# ltc1420_adc.net
KiCad netlist of a schematic drawn in EAGLE
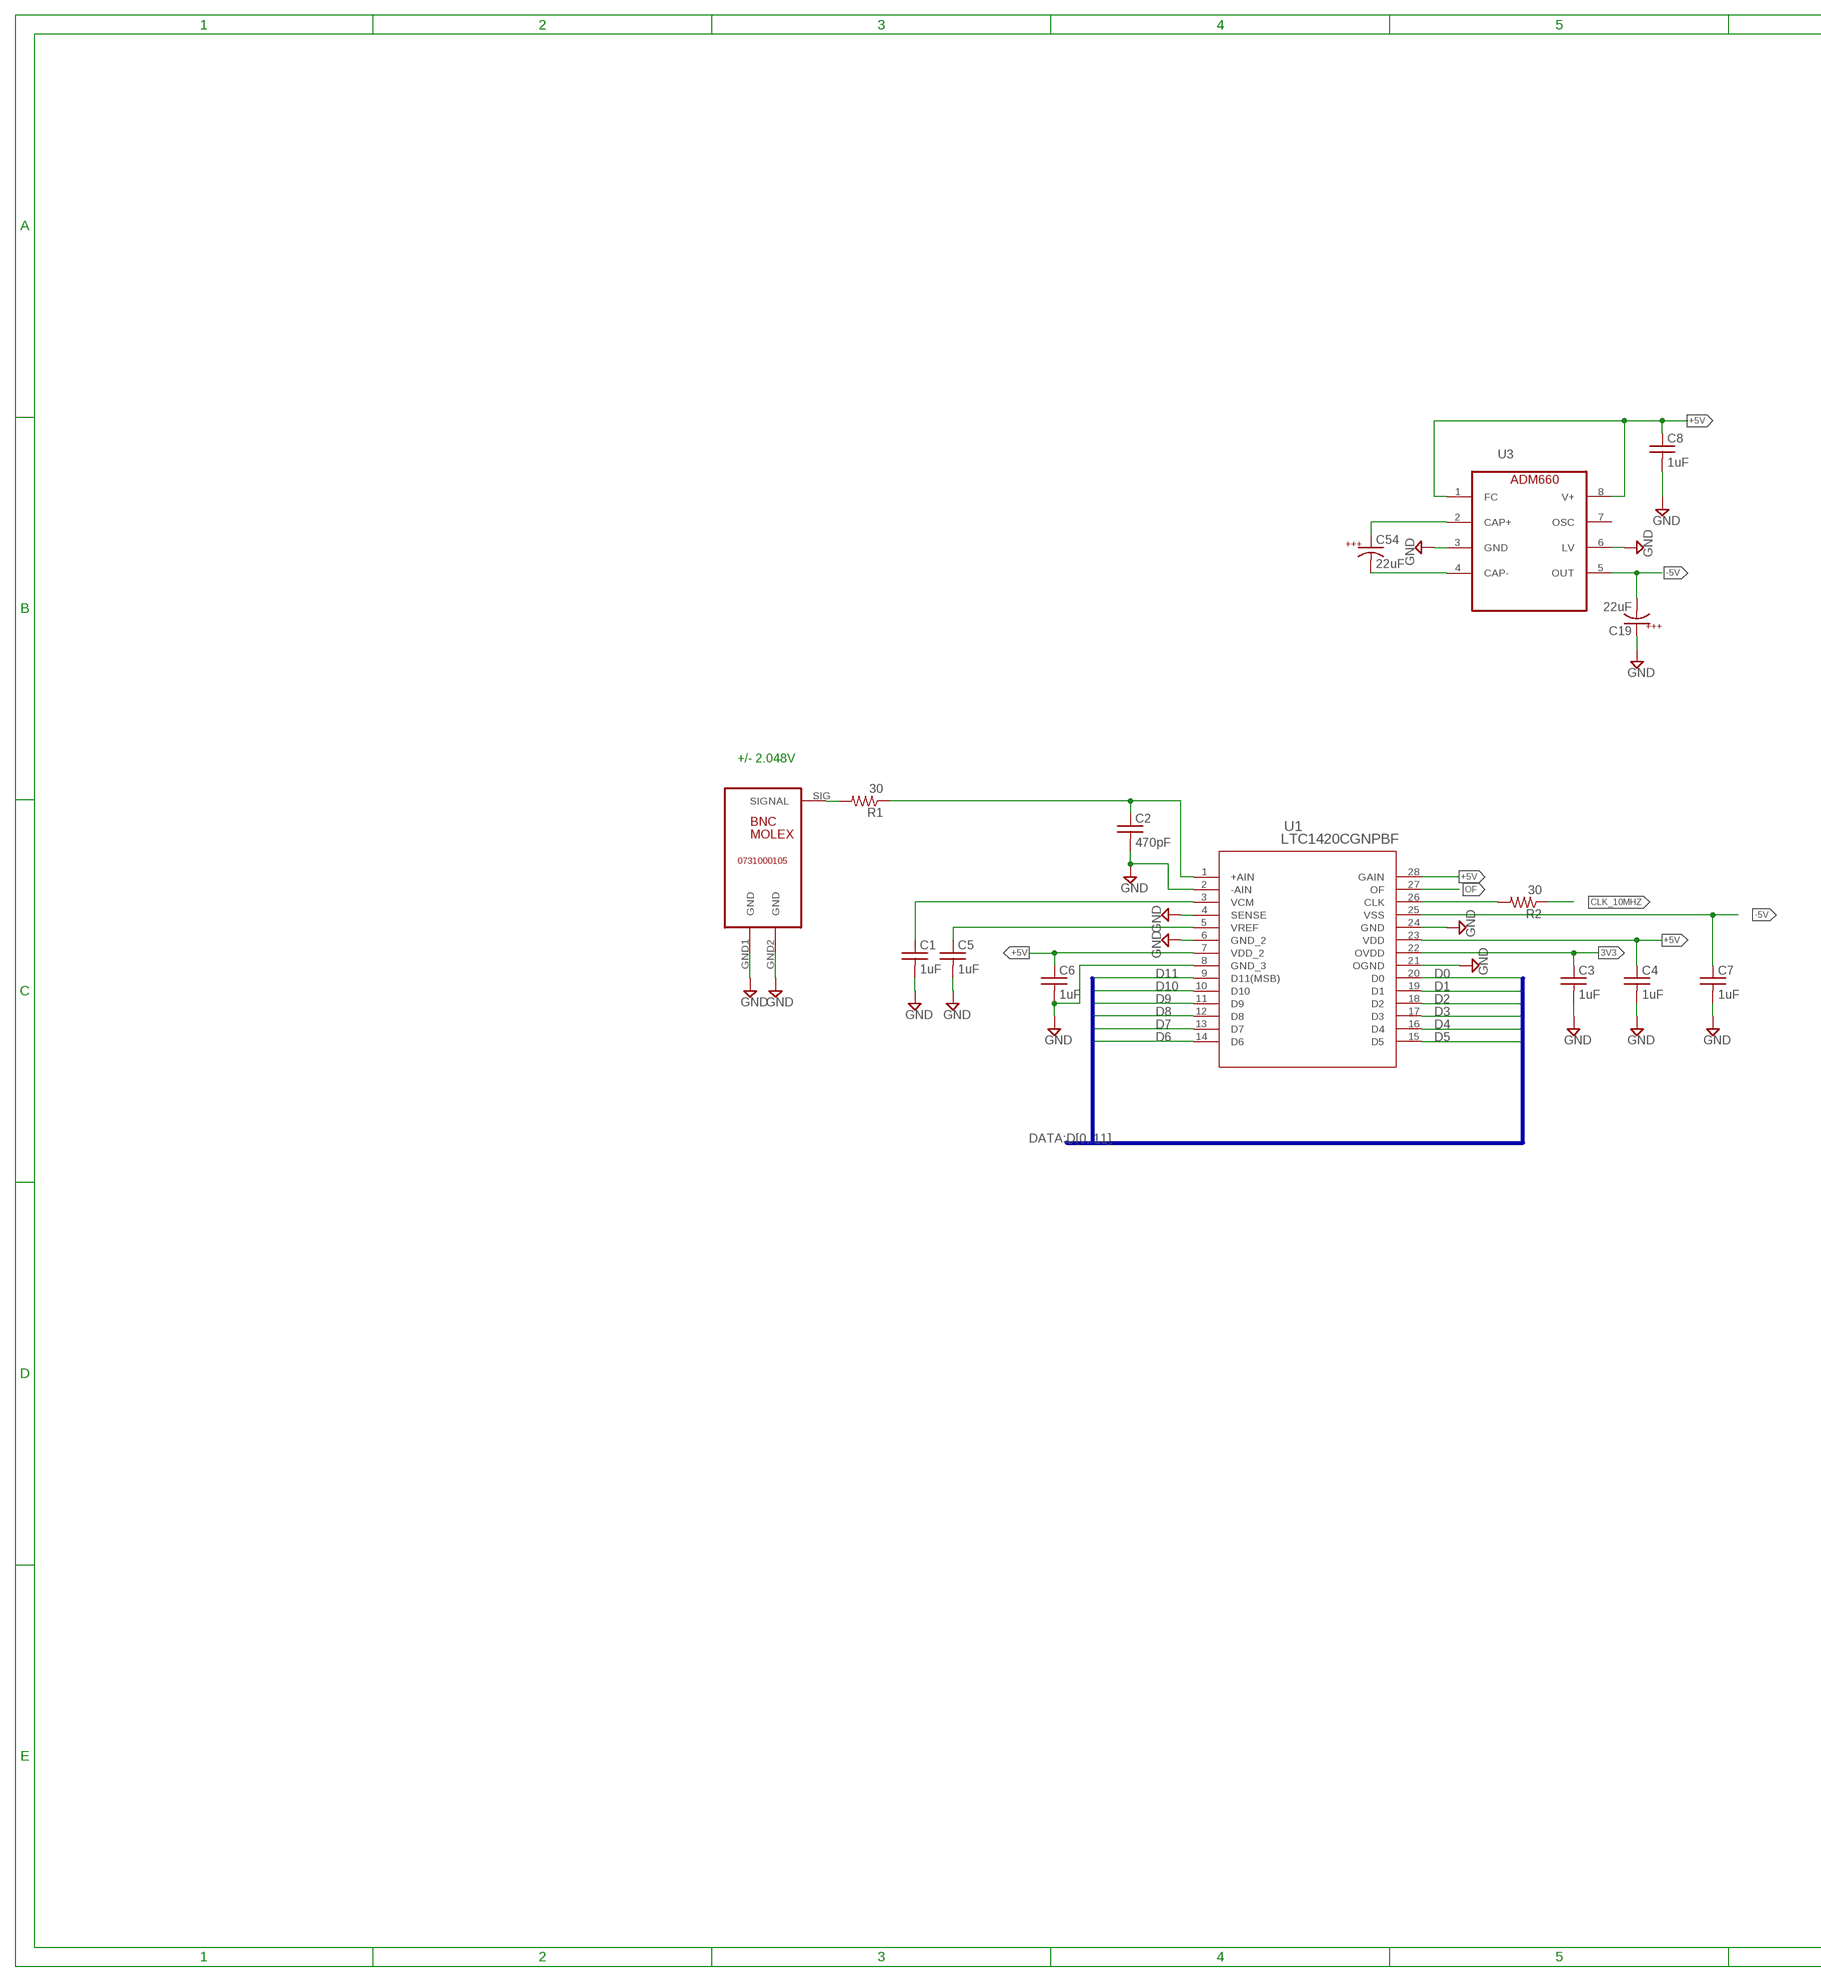
[diagram p0: schematic, sheet 1, part 1 of 2]
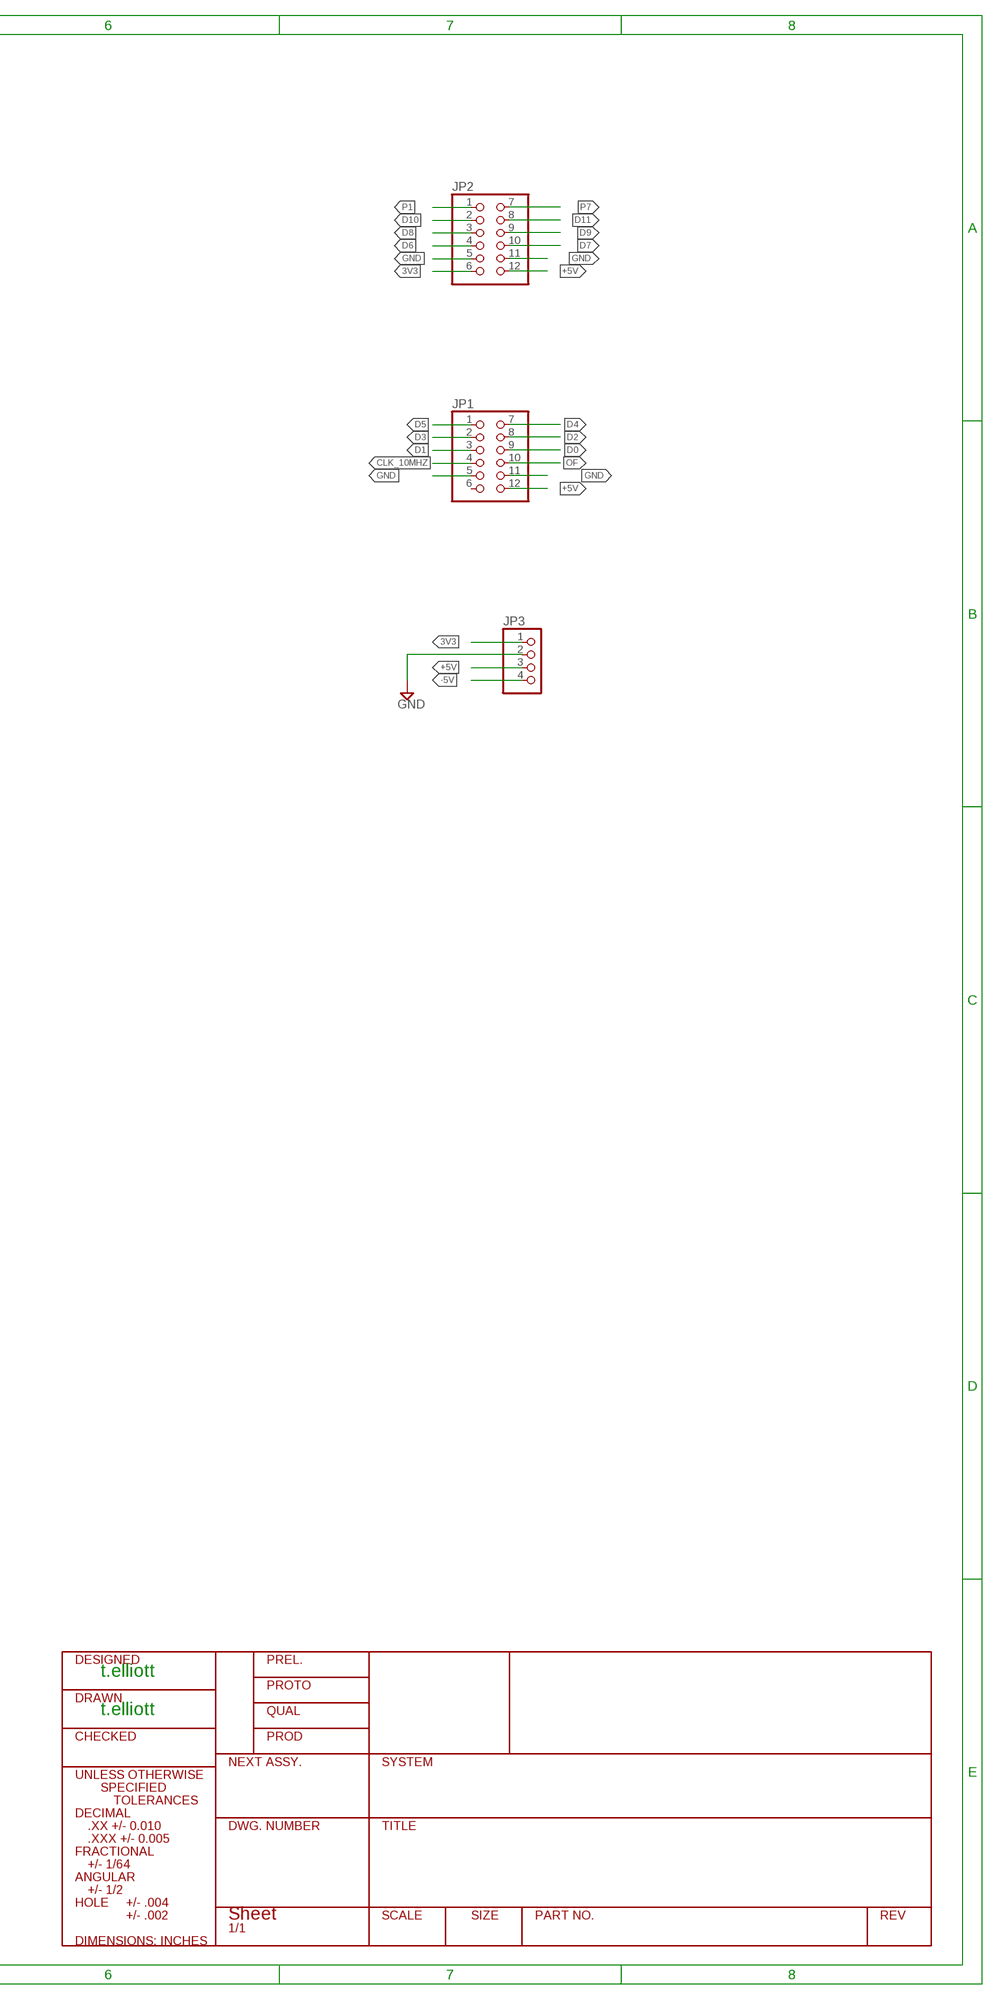
[diagram p1: schematic, sheet 1, part 2 of 2]

(export (version "E")
  (design (tool "Eeschema 10.0.6"))
  (components
    (comp (ref "C1")
      (value "1uF")
      (footprint "eagle-import:C0603")
      (libsource (lib "eagle-import") (part "C-USC0603"))
    )
    (comp (ref "C2")
      (value "470pF")
      (footprint "eagle-import:C0603")
      (libsource (lib "eagle-import") (part "C-USC0603"))
    )
    (comp (ref "C3")
      (value "1uF")
      (footprint "eagle-import:C0603")
      (libsource (lib "eagle-import") (part "C-USC0603"))
    )
    (comp (ref "C4")
      (value "1uF")
      (footprint "eagle-import:C0603")
      (libsource (lib "eagle-import") (part "C-USC0603"))
    )
    (comp (ref "C5")
      (value "1uF")
      (footprint "eagle-import:C0603")
      (libsource (lib "eagle-import") (part "C-USC0603"))
    )
    (comp (ref "C6")
      (value "1uF")
      (footprint "eagle-import:C0603")
      (libsource (lib "eagle-import") (part "C-USC0603"))
    )
    (comp (ref "C7")
      (value "1uF")
      (footprint "eagle-import:C0603")
      (libsource (lib "eagle-import") (part "C-USC0603"))
    )
    (comp (ref "C8")
      (value "1uF")
      (footprint "eagle-import:C0603")
      (libsource (lib "eagle-import") (part "C-USC0603"))
    )
    (comp (ref "C19")
      (value "22uF")
      (footprint "eagle-import:1210K")
      (libsource (lib "eagle-import") (part "CAPACITOR1210K"))
    )
    (comp (ref "C54")
      (value "22uF")
      (footprint "eagle-import:1210K")
      (libsource (lib "eagle-import") (part "CAPACITOR1210K"))
    )
    (comp (ref "J1")
      (value "0731000105_MOLEX_BNC")
      (footprint "eagle-import:BNC")
      (libsource (lib "eagle-import") (part "0731000105_MOLEX_BNC"))
    )
    (comp (ref "JP1")
      (value "PINHD-2X6")
      (footprint "eagle-import:2X06")
      (libsource (lib "eagle-import") (part "PINHD-2X6"))
    )
    (comp (ref "JP2")
      (value "PINHD-2X6")
      (footprint "eagle-import:2X06")
      (libsource (lib "eagle-import") (part "PINHD-2X6"))
    )
    (comp (ref "JP3")
      (value "PINHD-1X4")
      (footprint "eagle-import:1X04")
      (libsource (lib "eagle-import") (part "PINHD-1X4"))
    )
    (comp (ref "R1")
      (value "30")
      (footprint "eagle-import:R0402")
      (libsource (lib "eagle-import") (part "R-US_R0402"))
    )
    (comp (ref "R2")
      (value "30")
      (footprint "eagle-import:R0402")
      (libsource (lib "eagle-import") (part "R-US_R0402"))
    )
    (comp (ref "U1")
      (value "LTC1420CGNPBF")
      (footprint "eagle-import:SSOP-28_GN")
      (fields (field (name "MANUFACTURER_PART_NUMBER") "ltc1420cgn#pbf"))
      (libsource (lib "eagle-import") (part "LTC1420CGNPBF"))
    )
    (comp (ref "U3")
      (value "ADM660")
      (footprint "eagle-import:SO8")
      (libsource (lib "eagle-import") (part "ADM660"))
    )
  )
  (nets
    (net (code "13") (name "+5V") (class "Default")
      (node (ref "C4") (pin "1") (pinfunction "1_1") (pintype "passive"))
      (node (ref "C6") (pin "1") (pinfunction "1_1") (pintype "passive"))
      (node (ref "C8") (pin "1") (pinfunction "1_1") (pintype "passive"))
      (node (ref "JP1") (pin "12") (pinfunction "12_12") (pintype "passive"))
      (node (ref "JP2") (pin "12") (pinfunction "12_12") (pintype "passive"))
      (node (ref "JP3") (pin "3") (pinfunction "3_3") (pintype "passive"))
      (node (ref "U1") (pin "23") (pinfunction "VDD_23") (pintype "power_in"))
      (node (ref "U1") (pin "28") (pinfunction "GAIN_28") (pintype "input"))
      (node (ref "U1") (pin "7") (pinfunction "VDD_2_7") (pintype "power_in"))
      (node (ref "U3") (pin "1") (pinfunction "FC_1") (pintype "passive"))
      (node (ref "U3") (pin "8") (pinfunction "V+_8") (pintype "passive"))
    )
    (net (code "14") (name "-5V") (class "Default")
      (node (ref "C19") (pin "C") (pinfunction "C_C") (pintype "passive"))
      (node (ref "C7") (pin "1") (pinfunction "1_1") (pintype "passive"))
      (node (ref "JP3") (pin "4") (pinfunction "4_4") (pintype "passive"))
      (node (ref "U1") (pin "25") (pinfunction "VSS_25") (pintype "power_in"))
      (node (ref "U3") (pin "5") (pinfunction "OUT_5") (pintype "passive"))
    )
    (net (code "16") (name "3V3") (class "Default")
      (node (ref "C3") (pin "1") (pinfunction "1_1") (pintype "passive"))
      (node (ref "JP2") (pin "6") (pinfunction "11_6") (pintype "passive"))
      (node (ref "JP3") (pin "1") (pinfunction "1_1") (pintype "passive"))
      (node (ref "U1") (pin "22") (pinfunction "OVDD_22") (pintype "power_in"))
    )
    (net (code "17") (name "CLK_10MHZ") (class "Default")
      (node (ref "JP1") (pin "4") (pinfunction "7_4") (pintype "passive"))
      (node (ref "R2") (pin "1") (pinfunction "1_1") (pintype "passive"))
    )
    (net (code "18") (name "D0") (class "Default")
      (node (ref "JP1") (pin "9") (pinfunction "6_9") (pintype "passive"))
      (node (ref "U1") (pin "20") (pinfunction "D0_20") (pintype "output"))
    )
    (net (code "19") (name "D1") (class "Default")
      (node (ref "JP1") (pin "3") (pinfunction "5_3") (pintype "passive"))
      (node (ref "U1") (pin "19") (pinfunction "D1_19") (pintype "output"))
    )
    (net (code "20") (name "D2") (class "Default")
      (node (ref "JP1") (pin "8") (pinfunction "4_8") (pintype "passive"))
      (node (ref "U1") (pin "18") (pinfunction "D2_18") (pintype "output"))
    )
    (net (code "21") (name "D3") (class "Default")
      (node (ref "JP1") (pin "2") (pinfunction "3_2") (pintype "passive"))
      (node (ref "U1") (pin "17") (pinfunction "D3_17") (pintype "output"))
    )
    (net (code "22") (name "D4") (class "Default")
      (node (ref "JP1") (pin "7") (pinfunction "2_7") (pintype "passive"))
      (node (ref "U1") (pin "16") (pinfunction "D4_16") (pintype "output"))
    )
    (net (code "23") (name "D5") (class "Default")
      (node (ref "JP1") (pin "1") (pinfunction "1_1") (pintype "passive"))
      (node (ref "U1") (pin "15") (pinfunction "D5_15") (pintype "output"))
    )
    (net (code "24") (name "D6") (class "Default")
      (node (ref "JP2") (pin "4") (pinfunction "7_4") (pintype "passive"))
      (node (ref "U1") (pin "14") (pinfunction "D6_14") (pintype "output"))
    )
    (net (code "25") (name "D7") (class "Default")
      (node (ref "JP2") (pin "10") (pinfunction "8_10") (pintype "passive"))
      (node (ref "U1") (pin "13") (pinfunction "D7_13") (pintype "output"))
    )
    (net (code "26") (name "D8") (class "Default")
      (node (ref "JP2") (pin "3") (pinfunction "5_3") (pintype "passive"))
      (node (ref "U1") (pin "12") (pinfunction "D8_12") (pintype "output"))
    )
    (net (code "27") (name "D9") (class "Default")
      (node (ref "JP2") (pin "9") (pinfunction "6_9") (pintype "passive"))
      (node (ref "U1") (pin "11") (pinfunction "D9_11") (pintype "output"))
    )
    (net (code "28") (name "D10") (class "Default")
      (node (ref "JP2") (pin "2") (pinfunction "3_2") (pintype "passive"))
      (node (ref "U1") (pin "10") (pinfunction "D10_10") (pintype "output"))
    )
    (net (code "29") (name "D11") (class "Default")
      (node (ref "JP2") (pin "8") (pinfunction "4_8") (pintype "passive"))
      (node (ref "U1") (pin "9") (pinfunction "D11(MSB)_9") (pintype "output"))
    )
    (net (code "30") (name "GND") (class "Default")
      (node (ref "C1") (pin "2") (pinfunction "2_2") (pintype "passive"))
      (node (ref "C19") (pin "A") (pinfunction "A_A") (pintype "passive"))
      (node (ref "C2") (pin "2") (pinfunction "2_2") (pintype "passive"))
      (node (ref "C3") (pin "2") (pinfunction "2_2") (pintype "passive"))
      (node (ref "C4") (pin "2") (pinfunction "2_2") (pintype "passive"))
      (node (ref "C5") (pin "2") (pinfunction "2_2") (pintype "passive"))
      (node (ref "C6") (pin "2") (pinfunction "2_2") (pintype "passive"))
      (node (ref "C7") (pin "2") (pinfunction "2_2") (pintype "passive"))
      (node (ref "C8") (pin "2") (pinfunction "2_2") (pintype "passive"))
      (node (ref "J1") (pin "GND1") (pinfunction "GND_GND1") (pintype "passive"))
      (node (ref "J1") (pin "GND2") (pinfunction "GND_GND2") (pintype "passive"))
      (node (ref "JP1") (pin "11") (pinfunction "10_11") (pintype "passive"))
      (node (ref "JP1") (pin "5") (pinfunction "9_5") (pintype "passive"))
      (node (ref "JP2") (pin "11") (pinfunction "10_11") (pintype "passive"))
      (node (ref "JP2") (pin "5") (pinfunction "9_5") (pintype "passive"))
      (node (ref "JP3") (pin "2") (pinfunction "2_2") (pintype "passive"))
      (node (ref "U1") (pin "2") (pinfunction "-AIN_2") (pintype "input"))
      (node (ref "U1") (pin "21") (pinfunction "OGND_21") (pintype "power_in"))
      (node (ref "U1") (pin "24") (pinfunction "GND_24") (pintype "power_in"))
      (node (ref "U1") (pin "4") (pinfunction "SENSE_4") (pintype "passive"))
      (node (ref "U1") (pin "6") (pinfunction "GND_2_6") (pintype "power_in"))
      (node (ref "U1") (pin "8") (pinfunction "GND_3_8") (pintype "power_in"))
      (node (ref "U3") (pin "3") (pinfunction "GND_3") (pintype "passive"))
      (node (ref "U3") (pin "6") (pinfunction "LV_6") (pintype "passive"))
    )
    (net (code "31") (name "Net-(J1-SIGNAL)") (class "Default")
      (node (ref "J1") (pin "SIG") (pinfunction "SIGNAL_SIG") (pintype "passive"))
      (node (ref "R1") (pin "2") (pinfunction "2_2") (pintype "passive"))
    )
    (net (code "32") (name "Net-(U1-+AIN)") (class "Default")
      (node (ref "C2") (pin "1") (pinfunction "1_1") (pintype "passive"))
      (node (ref "R1") (pin "1") (pinfunction "1_1") (pintype "passive"))
      (node (ref "U1") (pin "1") (pinfunction "+AIN_1") (pintype "input"))
    )
    (net (code "33") (name "Net-(U1-CLK)") (class "Default")
      (node (ref "R2") (pin "2") (pinfunction "2_2") (pintype "passive"))
      (node (ref "U1") (pin "26") (pinfunction "CLK_26") (pintype "passive"))
    )
    (net (code "34") (name "Net-(U1-VCM)") (class "Default")
      (node (ref "C1") (pin "1") (pinfunction "1_1") (pintype "passive"))
      (node (ref "U1") (pin "3") (pinfunction "VCM_3") (pintype "output"))
    )
    (net (code "35") (name "Net-(U1-VREF)") (class "Default")
      (node (ref "C5") (pin "1") (pinfunction "1_1") (pintype "passive"))
      (node (ref "U1") (pin "5") (pinfunction "VREF_5") (pintype "power_in"))
    )
    (net (code "36") (name "Net-(U3-CAP+)") (class "Default")
      (node (ref "C54") (pin "A") (pinfunction "A_A") (pintype "passive"))
      (node (ref "U3") (pin "2") (pinfunction "CAP+_2") (pintype "passive"))
    )
    (net (code "37") (name "Net-(U3-CAP-)") (class "Default")
      (node (ref "C54") (pin "C") (pinfunction "C_C") (pintype "passive"))
      (node (ref "U3") (pin "4") (pinfunction "CAP-_4") (pintype "passive"))
    )
    (net (code "38") (name "OF") (class "Default")
      (node (ref "JP1") (pin "10") (pinfunction "8_10") (pintype "passive"))
      (node (ref "U1") (pin "27") (pinfunction "OF_27") (pintype "output"))
    )
    (net (code "39") (name "P1") (class "Default")
      (node (ref "JP2") (pin "1") (pinfunction "1_1") (pintype "passive"))
    )
    (net (code "40") (name "P7") (class "Default")
      (node (ref "JP2") (pin "7") (pinfunction "2_7") (pintype "passive"))
    )
    (net (code "41") (name "unconnected-(JP1-11-Pad6)") (class "Default")
      (node (ref "JP1") (pin "6") (pinfunction "11_6") (pintype "passive"))
    )
    (net (code "42") (name "unconnected-(U3-OSC-Pad7)") (class "Default")
      (node (ref "U3") (pin "7") (pinfunction "OSC_7") (pintype "passive"))
    )
  )
)
